# microcontroller_reset_button.net
KiCad netlist of a schematic drawn in Altium Designer
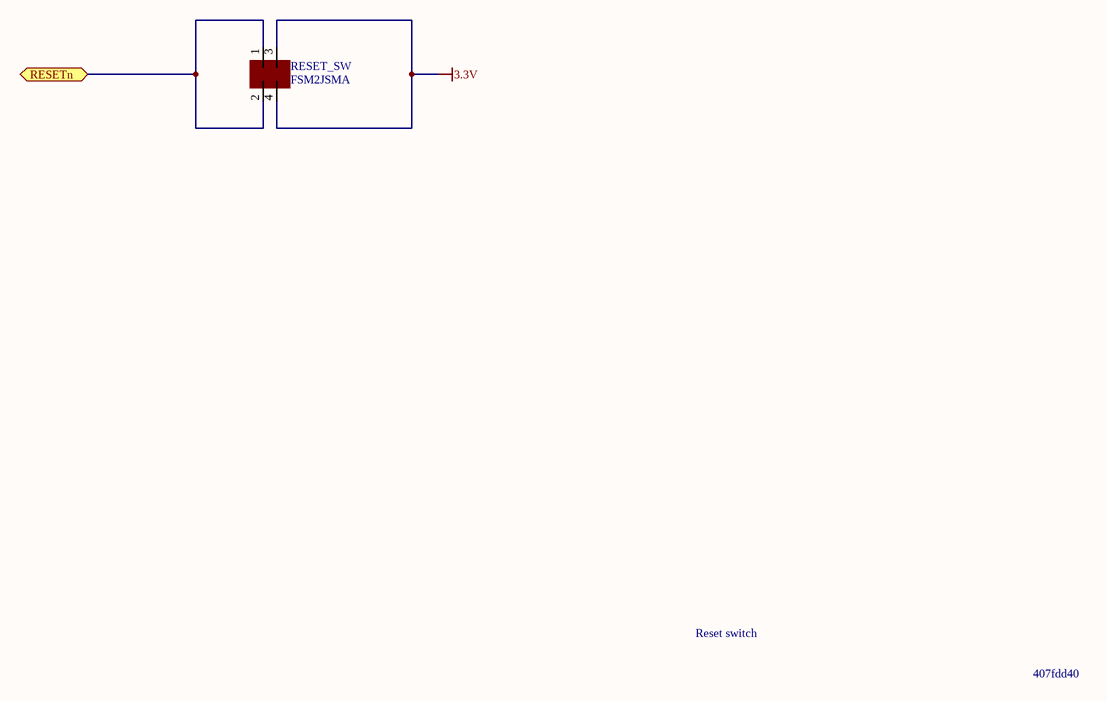
[diagram p0: microcontroller_reset_button.schdoc]

(export (version "E")
  (design (tool "Eeschema 10.0.6"))
  (components
    (comp (ref "RESET_SW")
      (value "FSM2JSMA")
      (footprint "Button")
      (libsource (lib "switch-button") (part "switch-button"))
    )
  )
  (nets
    (net (code "1") (name "/RESETn") (class "Default")
      (node (ref "RESET_SW") (pin "1") (pinfunction "1_1") (pintype "power_in"))
      (node (ref "RESET_SW") (pin "2") (pinfunction "2_2") (pintype "power_in"))
    )
    (net (code "2") (name "3.3V") (class "Default")
      (node (ref "RESET_SW") (pin "3") (pinfunction "3_3") (pintype "power_in"))
      (node (ref "RESET_SW") (pin "4") (pinfunction "4_4") (pintype "power_in"))
    )
  )
)
